# MUV_Interface_pcb.net
KiCad netlist of a schematic drawn in EAGLE
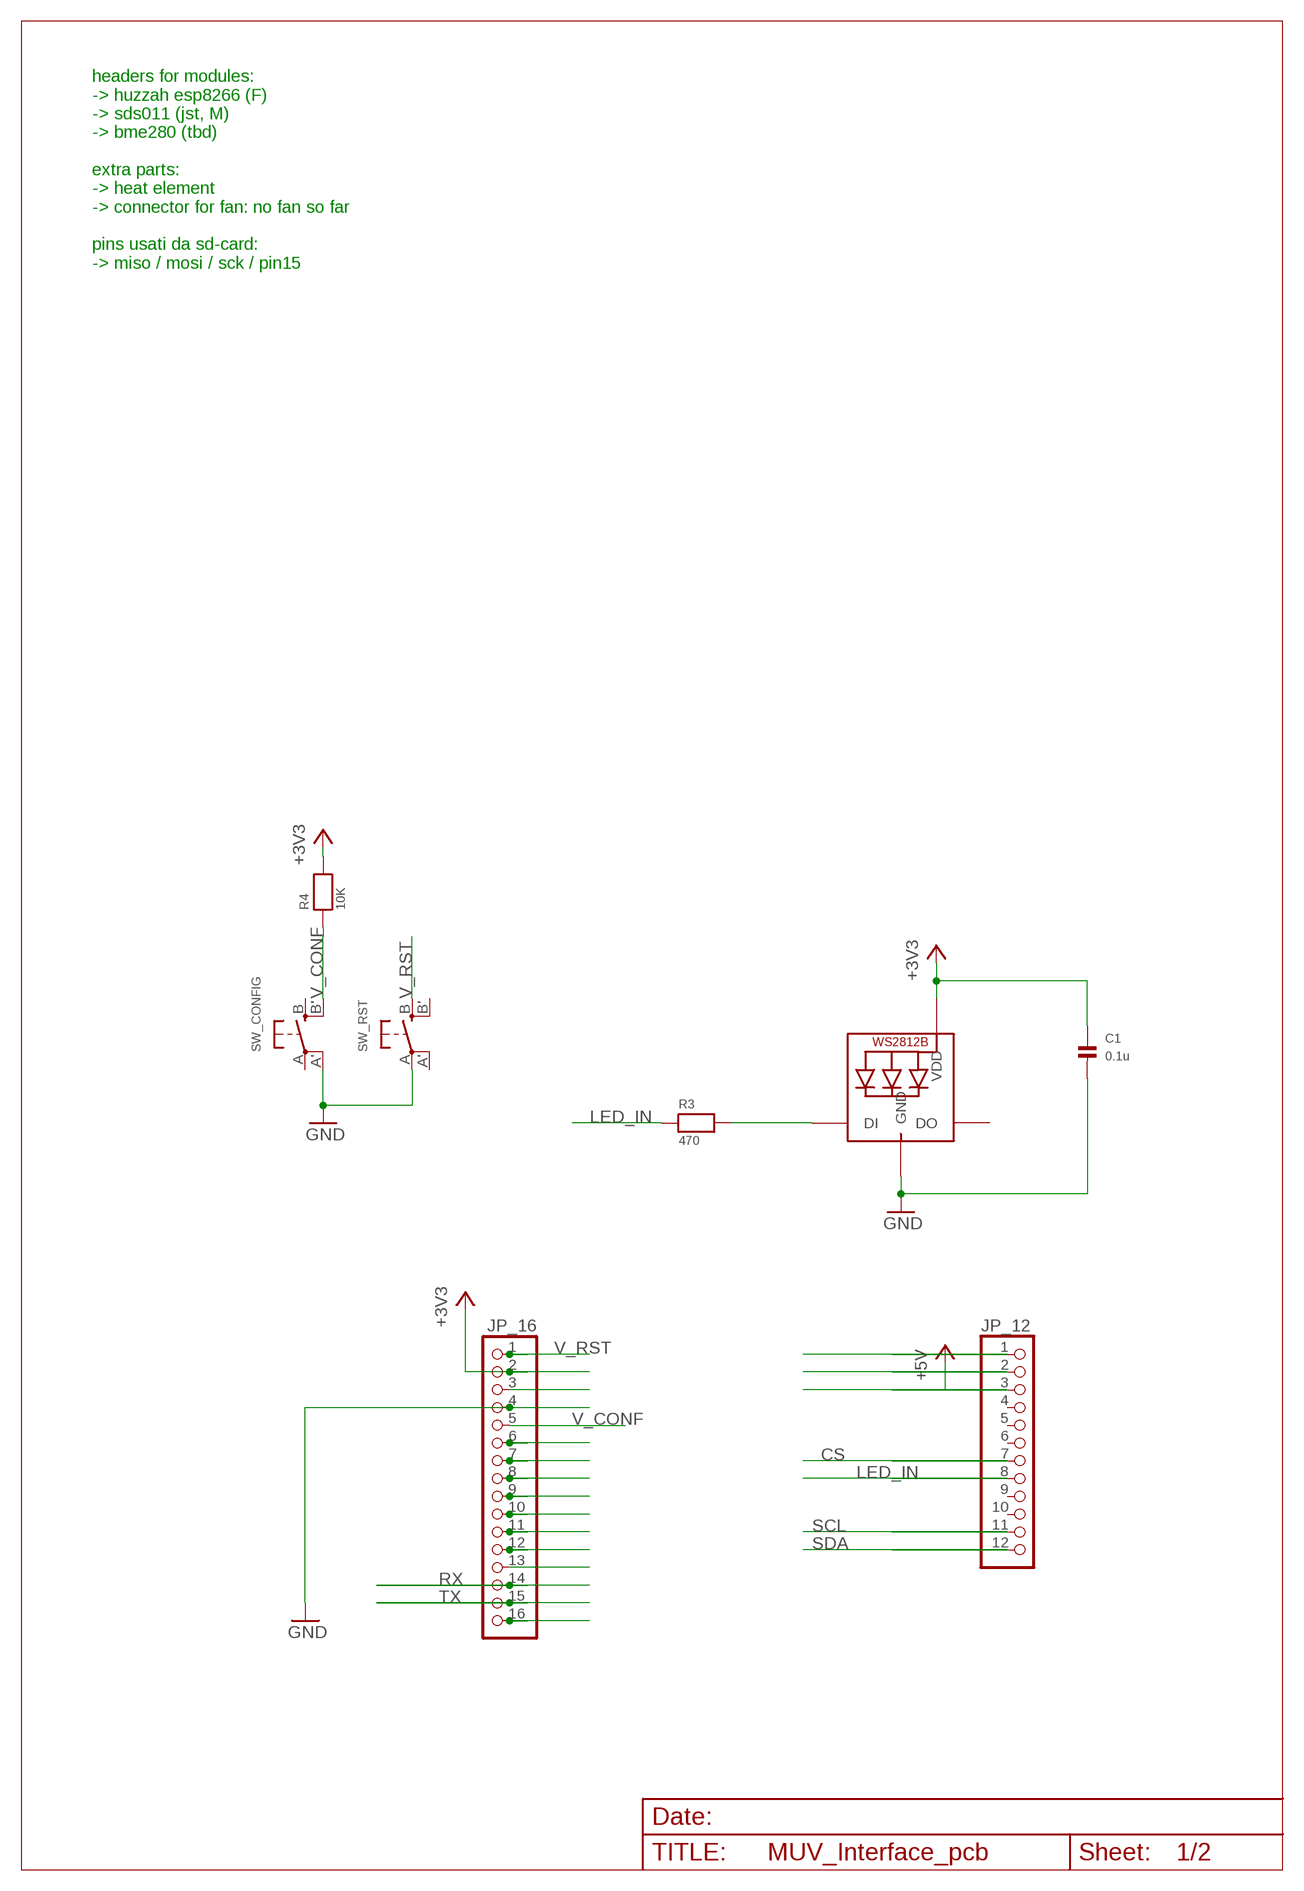
[diagram p0: schematic, sheet 1]

(export (version "E")
  (design (tool "Eeschema 10.0.6"))
  (components
    (comp (ref "C1")
      (value "0.1u")
      (footprint "eagle-import:1206")
      (libsource (lib "eagle-import") (part "CAP_CERAMIC1206"))
    )
    (comp (ref "JP_12")
      (value "HEADER-1X12OVAL")
      (footprint "eagle-import:1X12_OVAL")
      (libsource (lib "eagle-import") (part "HEADER-1X12OVAL"))
    )
    (comp (ref "JP_16")
      (value "HEADER-1X16")
      (footprint "eagle-import:1X16_OVAL")
      (libsource (lib "eagle-import") (part "HEADER-1X16"))
    )
    (comp (ref "LED1")
      (value "WS2812B5050")
      (footprint "eagle-import:WS2812B")
      (libsource (lib "eagle-import") (part "WS2812B5050"))
    )
    (comp (ref "R3")
      (value "470")
      (footprint "eagle-import:1206")
      (libsource (lib "eagle-import") (part "RESISTOR1206"))
    )
    (comp (ref "R4")
      (value "10K")
      (footprint "eagle-import:1206")
      (libsource (lib "eagle-import") (part "RESISTOR1206"))
    )
    (comp (ref "SW_CONFIG")
      (value "SWITCH_TACT_SMT")
      (footprint "eagle-import:EVQ-Q2")
      (libsource (lib "eagle-import") (part "SWITCH_TACT_SMT"))
    )
    (comp (ref "SW_RST")
      (value "SWITCH_TACT_SMT")
      (footprint "eagle-import:EVQ-Q2")
      (libsource (lib "eagle-import") (part "SWITCH_TACT_SMT"))
    )
  )
  (nets
    (net (code "1") (name "+3V3") (class "Default")
      (node (ref "C1") (pin "1") (pinfunction "P$1_1") (pintype "passive"))
      (node (ref "JP_16") (pin "2") (pinfunction "2_2") (pintype "passive"))
      (node (ref "LED1") (pin "1-VDD") (pinfunction "VDD_1-VDD") (pintype "power_in"))
      (node (ref "R4") (pin "2") (pinfunction "2_2") (pintype "passive"))
    )
    (net (code "2") (name "+5V") (class "Default")
      (node (ref "JP_12") (pin "3") (pinfunction "3_3") (pintype "passive"))
    )
    (net (code "3") (name "CS") (class "Default")
      (node (ref "JP_12") (pin "7") (pinfunction "7_7") (pintype "passive"))
    )
    (net (code "4") (name "GND") (class "Default")
      (node (ref "C1") (pin "2") (pinfunction "P$2_2") (pintype "passive"))
      (node (ref "JP_16") (pin "4") (pinfunction "4_4") (pintype "passive"))
      (node (ref "LED1") (pin "3-GND") (pinfunction "GND_3-GND") (pintype "power_in"))
      (node (ref "SW_CONFIG") (pin "A'") (pinfunction "P1_A'") (pintype "passive"))
      (node (ref "SW_RST") (pin "A") (pinfunction "P_A") (pintype "passive"))
    )
    (net (code "5") (name "LED_IN") (class "Default")
      (node (ref "JP_12") (pin "8") (pinfunction "8_8") (pintype "passive"))
      (node (ref "R3") (pin "1") (pinfunction "1_1") (pintype "passive"))
    )
    (net (code "6") (name "Net-(LED1-DI)") (class "Default")
      (node (ref "LED1") (pin "4-DIN") (pinfunction "DI_4-DIN") (pintype "input"))
      (node (ref "R3") (pin "2") (pinfunction "2_2") (pintype "passive"))
    )
    (net (code "7") (name "RX") (class "Default")
      (node (ref "JP_16") (pin "14") (pinfunction "14_14") (pintype "passive"))
    )
    (net (code "8") (name "SCL") (class "Default")
      (node (ref "JP_12") (pin "11") (pinfunction "11_11") (pintype "passive"))
    )
    (net (code "9") (name "SDA") (class "Default")
      (node (ref "JP_12") (pin "12") (pinfunction "12_12") (pintype "passive"))
    )
    (net (code "10") (name "TX") (class "Default")
      (node (ref "JP_16") (pin "15") (pinfunction "15_15") (pintype "passive"))
    )
    (net (code "11") (name "V_CONF") (class "Default")
      (node (ref "JP_16") (pin "5") (pinfunction "5_5") (pintype "passive"))
      (node (ref "R4") (pin "1") (pinfunction "1_1") (pintype "passive"))
      (node (ref "SW_CONFIG") (pin "B'") (pinfunction "S1_B'") (pintype "passive"))
    )
    (net (code "12") (name "V_RST") (class "Default")
      (node (ref "JP_16") (pin "1") (pinfunction "1_1") (pintype "passive"))
      (node (ref "SW_RST") (pin "B") (pinfunction "S_B") (pintype "passive"))
    )
    (net (code "13") (name "unconnected-(JP_12-Pad1)") (class "Default")
      (node (ref "JP_12") (pin "1") (pinfunction "1_1") (pintype "passive"))
    )
    (net (code "14") (name "unconnected-(JP_12-Pad2)") (class "Default")
      (node (ref "JP_12") (pin "2") (pinfunction "2_2") (pintype "passive"))
    )
    (net (code "15") (name "unconnected-(JP_12-Pad4)") (class "Default")
      (node (ref "JP_12") (pin "4") (pinfunction "4_4") (pintype "passive"))
    )
    (net (code "16") (name "unconnected-(JP_12-Pad5)") (class "Default")
      (node (ref "JP_12") (pin "5") (pinfunction "5_5") (pintype "passive"))
    )
    (net (code "17") (name "unconnected-(JP_12-Pad6)") (class "Default")
      (node (ref "JP_12") (pin "6") (pinfunction "6_6") (pintype "passive"))
    )
    (net (code "18") (name "unconnected-(JP_12-Pad9)") (class "Default")
      (node (ref "JP_12") (pin "9") (pinfunction "9_9") (pintype "passive"))
    )
    (net (code "19") (name "unconnected-(JP_12-Pad10)") (class "Default")
      (node (ref "JP_12") (pin "10") (pinfunction "10_10") (pintype "passive"))
    )
    (net (code "20") (name "unconnected-(JP_16-Pad3)") (class "Default")
      (node (ref "JP_16") (pin "3") (pinfunction "3_3") (pintype "passive"))
    )
    (net (code "21") (name "unconnected-(JP_16-Pad6)") (class "Default")
      (node (ref "JP_16") (pin "6") (pinfunction "6_6") (pintype "passive"))
    )
    (net (code "22") (name "unconnected-(JP_16-Pad7)") (class "Default")
      (node (ref "JP_16") (pin "7") (pinfunction "7_7") (pintype "passive"))
    )
    (net (code "23") (name "unconnected-(JP_16-Pad8)") (class "Default")
      (node (ref "JP_16") (pin "8") (pinfunction "8_8") (pintype "passive"))
    )
    (net (code "24") (name "unconnected-(JP_16-Pad9)") (class "Default")
      (node (ref "JP_16") (pin "9") (pinfunction "9_9") (pintype "passive"))
    )
    (net (code "25") (name "unconnected-(JP_16-Pad10)") (class "Default")
      (node (ref "JP_16") (pin "10") (pinfunction "10_10") (pintype "passive"))
    )
    (net (code "26") (name "unconnected-(JP_16-Pad11)") (class "Default")
      (node (ref "JP_16") (pin "11") (pinfunction "11_11") (pintype "passive"))
    )
    (net (code "27") (name "unconnected-(JP_16-Pad12)") (class "Default")
      (node (ref "JP_16") (pin "12") (pinfunction "12_12") (pintype "passive"))
    )
    (net (code "28") (name "unconnected-(JP_16-Pad13)") (class "Default")
      (node (ref "JP_16") (pin "13") (pinfunction "13_13") (pintype "passive"))
    )
    (net (code "29") (name "unconnected-(JP_16-Pad16)") (class "Default")
      (node (ref "JP_16") (pin "16") (pinfunction "16_16") (pintype "passive"))
    )
    (net (code "30") (name "unconnected-(LED1-DO-Pad2-DOUT)") (class "Default")
      (node (ref "LED1") (pin "2-DOUT") (pinfunction "DO_2-DOUT") (pintype "output"))
    )
    (net (code "31") (name "unconnected-(SW_CONFIG-P-PadA)") (class "Default")
      (node (ref "SW_CONFIG") (pin "A") (pinfunction "P_A") (pintype "passive"))
    )
    (net (code "32") (name "unconnected-(SW_CONFIG-S-PadB)") (class "Default")
      (node (ref "SW_CONFIG") (pin "B") (pinfunction "S_B") (pintype "passive"))
    )
    (net (code "33") (name "unconnected-(SW_RST-P1-PadA')") (class "Default")
      (node (ref "SW_RST") (pin "A'") (pinfunction "P1_A'") (pintype "passive"))
    )
    (net (code "34") (name "unconnected-(SW_RST-S1-PadB')") (class "Default")
      (node (ref "SW_RST") (pin "B'") (pinfunction "S1_B'") (pintype "passive"))
    )
  )
)
